# DTR-1_v2021-05-06.net
KiCad netlist of a schematic drawn in EAGLE
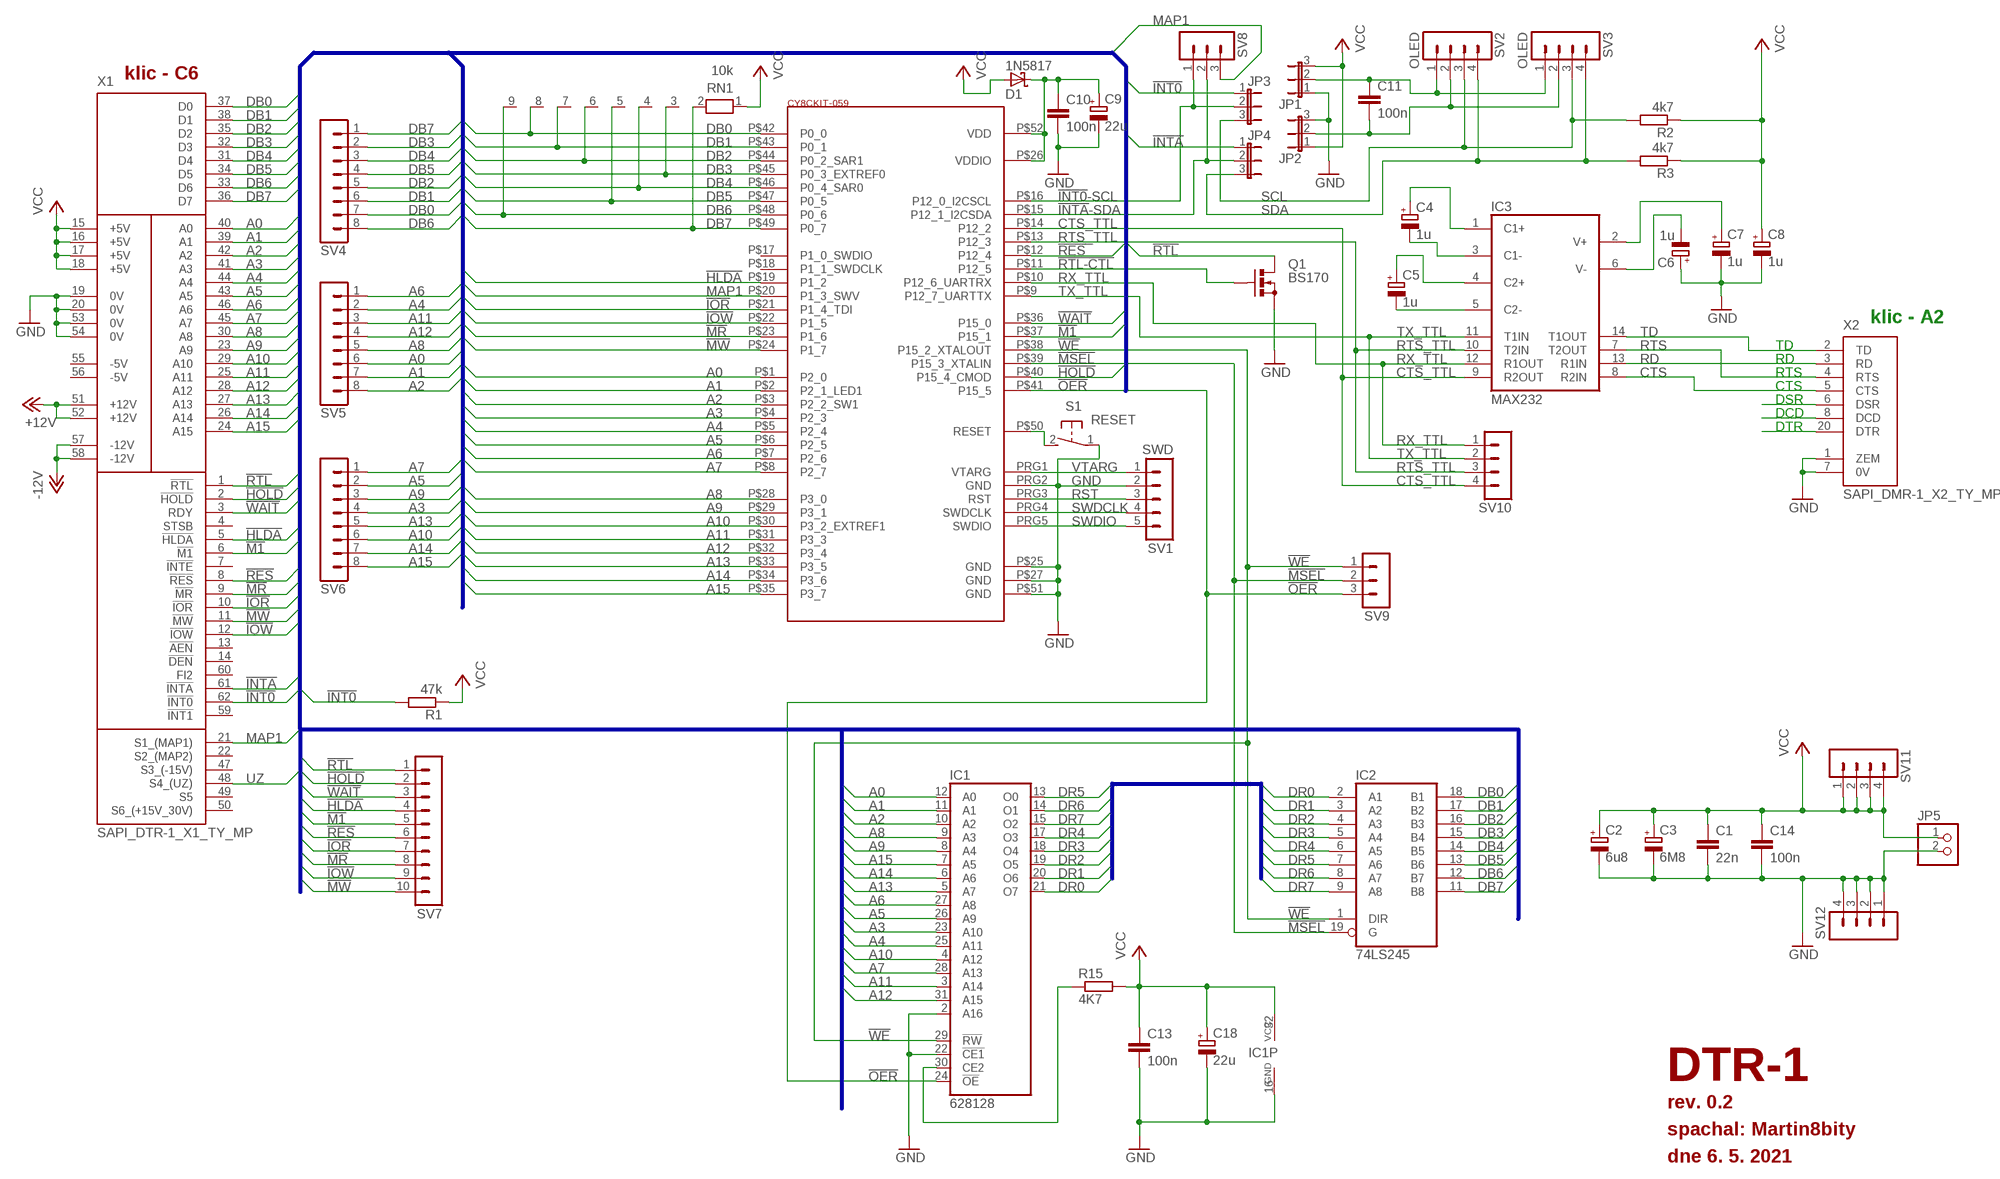
[diagram p0: schematic, sheet 1]

(export (version "E")
  (design (tool "Eeschema 10.0.6"))
  (components
    (comp (ref "C1")
      (value "22n")
      (footprint "eagle-import:C025-024X044")
      (libsource (lib "eagle-import") (part "C-EU025-024X044"))
    )
    (comp (ref "C2")
      (value "6u8")
      (footprint "eagle-import:E5-4")
      (libsource (lib "eagle-import") (part "CPOL-EUE5-4"))
    )
    (comp (ref "C3")
      (value "6M8")
      (footprint "eagle-import:E2,5-5")
      (libsource (lib "eagle-import") (part "CPOL-EUE2.5-5"))
    )
    (comp (ref "C4")
      (value "1u")
      (footprint "eagle-import:E2,5-5")
      (libsource (lib "eagle-import") (part "CPOL-EUE2.5-5"))
    )
    (comp (ref "C5")
      (value "1u")
      (footprint "eagle-import:E2,5-5")
      (libsource (lib "eagle-import") (part "CPOL-EUE2.5-5"))
    )
    (comp (ref "C6")
      (value "1u")
      (footprint "eagle-import:E2,5-5")
      (libsource (lib "eagle-import") (part "CPOL-EUE2.5-5"))
    )
    (comp (ref "C7")
      (value "1u")
      (footprint "eagle-import:E2,5-5")
      (libsource (lib "eagle-import") (part "CPOL-EUE2.5-5"))
    )
    (comp (ref "C8")
      (value "1u")
      (footprint "eagle-import:E2,5-5")
      (libsource (lib "eagle-import") (part "CPOL-EUE2.5-5"))
    )
    (comp (ref "C9")
      (value "22u")
      (footprint "eagle-import:E2,5-5")
      (libsource (lib "eagle-import") (part "CPOL-EUE2.5-5"))
    )
    (comp (ref "C10")
      (value "100n")
      (footprint "eagle-import:C025-024X044")
      (libsource (lib "eagle-import") (part "C-EU025-024X044"))
    )
    (comp (ref "C11")
      (value "100n")
      (footprint "eagle-import:C050-025X075")
      (libsource (lib "eagle-import") (part "C-EU050-025X075"))
    )
    (comp (ref "C13")
      (value "100n")
      (footprint "eagle-import:C025-024X044")
      (libsource (lib "eagle-import") (part "C-EU025-024X044"))
    )
    (comp (ref "C14")
      (value "100n")
      (footprint "eagle-import:C025-024X044")
      (libsource (lib "eagle-import") (part "C-EU025-024X044"))
    )
    (comp (ref "C18")
      (value "22u")
      (footprint "eagle-import:E2,5-5")
      (libsource (lib "eagle-import") (part "CPOL-EUE2.5-5"))
    )
    (comp (ref "D1")
      (value "1N5817")
      (footprint "eagle-import:DO41-7.6")
      (libsource (lib "eagle-import") (part "1N5817-B"))
    )
    (comp (ref "IC1")
      (value "628128")
      (footprint "eagle-import:DIL32")
      (libsource (lib "eagle-import") (part "TC551001CP"))
    )
    (comp (ref "IC2")
      (value "74LS245")
      (footprint "eagle-import:DIL20")
      (libsource (lib "eagle-import") (part "74245NLS"))
    )
    (comp (ref "IC3")
      (value "MAX232")
      (footprint "eagle-import:DIL16")
      (fields (field (name "MF") "MAXIM") (field (name "MPN") "MAX232ACPE+"))
      (libsource (lib "eagle-import") (part "MAX232"))
    )
    (comp (ref "JP1")
      (value "JP2E")
      (footprint "eagle-import:JP2")
      (libsource (lib "eagle-import") (part "JP2E"))
    )
    (comp (ref "JP2")
      (value "JP2E")
      (footprint "eagle-import:JP2")
      (libsource (lib "eagle-import") (part "JP2E"))
    )
    (comp (ref "JP3")
      (value "JP2E")
      (footprint "eagle-import:JP2")
      (libsource (lib "eagle-import") (part "JP2E"))
    )
    (comp (ref "JP4")
      (value "JP2E")
      (footprint "eagle-import:JP2")
      (libsource (lib "eagle-import") (part "JP2E"))
    )
    (comp (ref "JP5")
      (value "PINHD-1X2")
      (footprint "eagle-import:1X02")
      (libsource (lib "eagle-import") (part "PINHD-1X2"))
    )
    (comp (ref "Q1")
      (value "BS170")
      (footprint "eagle-import:SOT54E")
      (libsource (lib "eagle-import") (part "BS170"))
    )
    (comp (ref "R1")
      (value "47k")
      (footprint "eagle-import:0207_10")
      (libsource (lib "eagle-import") (part "R-EU_0207/10"))
    )
    (comp (ref "R2")
      (value "4k7")
      (footprint "eagle-import:0207_10")
      (libsource (lib "eagle-import") (part "R-EU_0207/10"))
    )
    (comp (ref "R3")
      (value "4k7")
      (footprint "eagle-import:0207_10")
      (libsource (lib "eagle-import") (part "R-EU_0207/10"))
    )
    (comp (ref "R15")
      (value "4K7")
      (footprint "eagle-import:0207_10")
      (libsource (lib "eagle-import") (part "R-EU_0207/10"))
    )
    (comp (ref "RN1")
      (value "10k")
      (footprint "eagle-import:RN-9")
      (libsource (lib "eagle-import") (part "RN08"))
    )
    (comp (ref "S1")
      (value "RESET")
      (footprint "eagle-import:B3F-31XX")
      (fields (field (name "MPN") "B3F-3100"))
      (libsource (lib "eagle-import") (part "31-XX"))
    )
    (comp (ref "SV1")
      (value "SWD")
      (footprint "eagle-import:MA05-1")
      (libsource (lib "eagle-import") (part "MA05-1"))
    )
    (comp (ref "SV2")
      (value "OLED")
      (footprint "eagle-import:MA04-1")
      (libsource (lib "eagle-import") (part "MA04-1"))
    )
    (comp (ref "SV3")
      (value "OLED")
      (footprint "eagle-import:MA04-1")
      (libsource (lib "eagle-import") (part "MA04-1"))
    )
    (comp (ref "SV4")
      (value "MA08-1")
      (footprint "eagle-import:MA08-1")
      (libsource (lib "eagle-import") (part "MA08-1"))
    )
    (comp (ref "SV5")
      (value "MA08-1")
      (footprint "eagle-import:MA08-1")
      (libsource (lib "eagle-import") (part "MA08-1"))
    )
    (comp (ref "SV6")
      (value "MA08-1")
      (footprint "eagle-import:MA08-1")
      (libsource (lib "eagle-import") (part "MA08-1"))
    )
    (comp (ref "SV7")
      (value "MA10-1")
      (footprint "eagle-import:MA10-1")
      (libsource (lib "eagle-import") (part "MA10-1"))
    )
    (comp (ref "SV8")
      (value "MA03-1")
      (footprint "eagle-import:MA03-1")
      (libsource (lib "eagle-import") (part "MA03-1"))
    )
    (comp (ref "SV9")
      (value "MA03-1")
      (footprint "eagle-import:MA03-1")
      (libsource (lib "eagle-import") (part "MA03-1"))
    )
    (comp (ref "SV10")
      (value "MA04-1")
      (footprint "eagle-import:MA04-1")
      (libsource (lib "eagle-import") (part "MA04-1"))
    )
    (comp (ref "SV11")
      (value "MA04-1")
      (footprint "eagle-import:MA04-1")
      (libsource (lib "eagle-import") (part "MA04-1"))
    )
    (comp (ref "SV12")
      (value "MA04-1")
      (footprint "eagle-import:MA04-1")
      (libsource (lib "eagle-import") (part "MA04-1"))
    )
    (comp (ref "U$1")
      (value "CY8CKIT-059")
      (footprint "eagle-import:PSOC-KIT-26")
      (libsource (lib "eagle-import") (part "CY8CKIT-059"))
    )
    (comp (ref "X1")
      (value "SAPI_DTR-1_X1_TY_MP")
      (footprint "eagle-import:TY5176211_DTR-1_X1")
      (libsource (lib "eagle-import") (part "SAPI_DTR-1_X1_TY_MP"))
    )
    (comp (ref "X2")
      (value "SAPI_DMR-1_X2_TY_MP")
      (footprint "eagle-import:TY5133011_DMR-1_X2")
      (libsource (lib "eagle-import") (part "SAPI_DMR-1_X2_TY_MP"))
    )
  )
  (nets
    (net (code "1") (name "+12V") (class "Default")
      (node (ref "X1") (pin "51") (pinfunction "+12V_51") (pintype "passive"))
      (node (ref "X1") (pin "52") (pinfunction "+12V_52") (pintype "passive"))
    )
    (net (code "2") (name "-12V") (class "Default")
      (node (ref "X1") (pin "57") (pinfunction "-12V_57") (pintype "passive"))
      (node (ref "X1") (pin "58") (pinfunction "-12V_58") (pintype "passive"))
    )
    (net (code "3") (name "/A0") (class "Default")
      (node (ref "IC1") (pin "12") (pinfunction "A0_12") (pintype "input"))
      (node (ref "SV5") (pin "6") (pinfunction "6_6") (pintype "passive"))
      (node (ref "U$1") (pin "P$1") (pinfunction "P2_0_P$1") (pintype "bidirectional"))
      (node (ref "X1") (pin "40") (pinfunction "A0_40") (pintype "passive"))
    )
    (net (code "4") (name "/A1") (class "Default")
      (node (ref "IC1") (pin "11") (pinfunction "A1_11") (pintype "input"))
      (node (ref "SV5") (pin "7") (pinfunction "7_7") (pintype "passive"))
      (node (ref "U$1") (pin "P$2") (pinfunction "P2_1_LED1_P$2") (pintype "bidirectional"))
      (node (ref "X1") (pin "39") (pinfunction "A1_39") (pintype "passive"))
    )
    (net (code "5") (name "/A2") (class "Default")
      (node (ref "IC1") (pin "10") (pinfunction "A2_10") (pintype "input"))
      (node (ref "SV5") (pin "8") (pinfunction "8_8") (pintype "passive"))
      (node (ref "U$1") (pin "P$3") (pinfunction "P2_2_SW1_P$3") (pintype "bidirectional"))
      (node (ref "X1") (pin "42") (pinfunction "A2_42") (pintype "passive"))
    )
    (net (code "6") (name "/A3") (class "Default")
      (node (ref "IC1") (pin "23") (pinfunction "A10_23") (pintype "input"))
      (node (ref "SV6") (pin "4") (pinfunction "4_4") (pintype "passive"))
      (node (ref "U$1") (pin "P$4") (pinfunction "P2_3_P$4") (pintype "bidirectional"))
      (node (ref "X1") (pin "41") (pinfunction "A3_41") (pintype "passive"))
    )
    (net (code "7") (name "/A4") (class "Default")
      (node (ref "IC1") (pin "25") (pinfunction "A11_25") (pintype "input"))
      (node (ref "SV5") (pin "2") (pinfunction "2_2") (pintype "passive"))
      (node (ref "U$1") (pin "P$5") (pinfunction "P2_4_P$5") (pintype "bidirectional"))
      (node (ref "X1") (pin "44") (pinfunction "A4_44") (pintype "passive"))
    )
    (net (code "8") (name "/A5") (class "Default")
      (node (ref "IC1") (pin "26") (pinfunction "A9_26") (pintype "input"))
      (node (ref "SV6") (pin "2") (pinfunction "2_2") (pintype "passive"))
      (node (ref "U$1") (pin "P$6") (pinfunction "P2_5_P$6") (pintype "bidirectional"))
      (node (ref "X1") (pin "43") (pinfunction "A5_43") (pintype "passive"))
    )
    (net (code "9") (name "/A6") (class "Default")
      (node (ref "IC1") (pin "27") (pinfunction "A8_27") (pintype "input"))
      (node (ref "SV5") (pin "1") (pinfunction "1_1") (pintype "passive"))
      (node (ref "U$1") (pin "P$7") (pinfunction "P2_6_P$7") (pintype "bidirectional"))
      (node (ref "X1") (pin "46") (pinfunction "A6_46") (pintype "passive"))
    )
    (net (code "10") (name "/A7") (class "Default")
      (node (ref "IC1") (pin "28") (pinfunction "A13_28") (pintype "input"))
      (node (ref "SV6") (pin "1") (pinfunction "1_1") (pintype "passive"))
      (node (ref "U$1") (pin "P$8") (pinfunction "P2_7_P$8") (pintype "bidirectional"))
      (node (ref "X1") (pin "45") (pinfunction "A7_45") (pintype "passive"))
    )
    (net (code "11") (name "/A8") (class "Default")
      (node (ref "IC1") (pin "9") (pinfunction "A3_9") (pintype "input"))
      (node (ref "SV5") (pin "5") (pinfunction "5_5") (pintype "passive"))
      (node (ref "U$1") (pin "P$28") (pinfunction "P3_0_P$28") (pintype "bidirectional"))
      (node (ref "X1") (pin "30") (pinfunction "A8_30") (pintype "passive"))
    )
    (net (code "12") (name "/A9") (class "Default")
      (node (ref "IC1") (pin "8") (pinfunction "A4_8") (pintype "input"))
      (node (ref "SV6") (pin "3") (pinfunction "3_3") (pintype "passive"))
      (node (ref "U$1") (pin "P$29") (pinfunction "P3_1_P$29") (pintype "bidirectional"))
      (node (ref "X1") (pin "23") (pinfunction "A9_23") (pintype "passive"))
    )
    (net (code "13") (name "/A10") (class "Default")
      (node (ref "IC1") (pin "4") (pinfunction "A12_4") (pintype "input"))
      (node (ref "SV6") (pin "6") (pinfunction "6_6") (pintype "passive"))
      (node (ref "U$1") (pin "P$30") (pinfunction "P3_2_EXTREF1_P$30") (pintype "bidirectional"))
      (node (ref "X1") (pin "29") (pinfunction "A10_29") (pintype "passive"))
    )
    (net (code "14") (name "/A11") (class "Default")
      (node (ref "IC1") (pin "3") (pinfunction "A14_3") (pintype "input"))
      (node (ref "SV5") (pin "3") (pinfunction "3_3") (pintype "passive"))
      (node (ref "U$1") (pin "P$31") (pinfunction "P3_3_P$31") (pintype "bidirectional"))
      (node (ref "X1") (pin "25") (pinfunction "A11_25") (pintype "passive"))
    )
    (net (code "15") (name "/A12") (class "Default")
      (node (ref "IC1") (pin "31") (pinfunction "A15_31") (pintype "input"))
      (node (ref "SV5") (pin "4") (pinfunction "4_4") (pintype "passive"))
      (node (ref "U$1") (pin "P$32") (pinfunction "P3_4_P$32") (pintype "bidirectional"))
      (node (ref "X1") (pin "28") (pinfunction "A12_28") (pintype "passive"))
    )
    (net (code "16") (name "/A13") (class "Default")
      (node (ref "IC1") (pin "5") (pinfunction "A7_5") (pintype "input"))
      (node (ref "SV6") (pin "5") (pinfunction "5_5") (pintype "passive"))
      (node (ref "U$1") (pin "P$33") (pinfunction "P3_5_P$33") (pintype "bidirectional"))
      (node (ref "X1") (pin "27") (pinfunction "A13_27") (pintype "passive"))
    )
    (net (code "17") (name "/A14") (class "Default")
      (node (ref "IC1") (pin "6") (pinfunction "A6_6") (pintype "input"))
      (node (ref "SV6") (pin "7") (pinfunction "7_7") (pintype "passive"))
      (node (ref "U$1") (pin "P$34") (pinfunction "P3_6_P$34") (pintype "bidirectional"))
      (node (ref "X1") (pin "26") (pinfunction "A14_26") (pintype "passive"))
    )
    (net (code "18") (name "/A15") (class "Default")
      (node (ref "IC1") (pin "7") (pinfunction "A5_7") (pintype "input"))
      (node (ref "SV6") (pin "8") (pinfunction "8_8") (pintype "passive"))
      (node (ref "U$1") (pin "P$35") (pinfunction "P3_7_P$35") (pintype "bidirectional"))
      (node (ref "X1") (pin "24") (pinfunction "A15_24") (pintype "passive"))
    )
    (net (code "19") (name "/CTS") (class "Default")
      (node (ref "IC3") (pin "8") (pinfunction "R2IN_8") (pintype "input"))
      (node (ref "X2") (pin "5") (pinfunction "CTS_5") (pintype "passive"))
    )
    (net (code "20") (name "/CTS_TTL") (class "Default")
      (node (ref "IC3") (pin "9") (pinfunction "R2OUT_9") (pintype "output"))
      (node (ref "SV10") (pin "4") (pinfunction "4_4") (pintype "passive"))
      (node (ref "U$1") (pin "P$14") (pinfunction "P12_2_P$14") (pintype "bidirectional"))
    )
    (net (code "21") (name "/DB0") (class "Default")
      (node (ref "IC2") (pin "18") (pinfunction "B1_18") (pintype "bidirectional"))
      (node (ref "RN1") (pin "8") (pinfunction "8_8") (pintype "passive"))
      (node (ref "SV4") (pin "7") (pinfunction "7_7") (pintype "passive"))
      (node (ref "U$1") (pin "P$42") (pinfunction "P0_0_P$42") (pintype "bidirectional"))
      (node (ref "X1") (pin "37") (pinfunction "D0_37") (pintype "passive"))
    )
    (net (code "22") (name "/DB1") (class "Default")
      (node (ref "IC2") (pin "17") (pinfunction "B2_17") (pintype "bidirectional"))
      (node (ref "RN1") (pin "7") (pinfunction "7_7") (pintype "passive"))
      (node (ref "SV4") (pin "6") (pinfunction "6_6") (pintype "passive"))
      (node (ref "U$1") (pin "P$43") (pinfunction "P0_1_P$43") (pintype "bidirectional"))
      (node (ref "X1") (pin "38") (pinfunction "D1_38") (pintype "passive"))
    )
    (net (code "23") (name "/DB2") (class "Default")
      (node (ref "IC2") (pin "16") (pinfunction "B3_16") (pintype "bidirectional"))
      (node (ref "RN1") (pin "6") (pinfunction "6_6") (pintype "passive"))
      (node (ref "SV4") (pin "5") (pinfunction "5_5") (pintype "passive"))
      (node (ref "U$1") (pin "P$44") (pinfunction "P0_2_SAR1_P$44") (pintype "bidirectional"))
      (node (ref "X1") (pin "35") (pinfunction "D2_35") (pintype "passive"))
    )
    (net (code "24") (name "/DB3") (class "Default")
      (node (ref "IC2") (pin "15") (pinfunction "B4_15") (pintype "bidirectional"))
      (node (ref "RN1") (pin "3") (pinfunction "3_3") (pintype "passive"))
      (node (ref "SV4") (pin "2") (pinfunction "2_2") (pintype "passive"))
      (node (ref "U$1") (pin "P$45") (pinfunction "P0_3_EXTREF0_P$45") (pintype "bidirectional"))
      (node (ref "X1") (pin "32") (pinfunction "D3_32") (pintype "passive"))
    )
    (net (code "25") (name "/DB4") (class "Default")
      (node (ref "IC2") (pin "14") (pinfunction "B5_14") (pintype "bidirectional"))
      (node (ref "RN1") (pin "4") (pinfunction "4_4") (pintype "passive"))
      (node (ref "SV4") (pin "3") (pinfunction "3_3") (pintype "passive"))
      (node (ref "U$1") (pin "P$46") (pinfunction "P0_4_SAR0_P$46") (pintype "bidirectional"))
      (node (ref "X1") (pin "31") (pinfunction "D4_31") (pintype "passive"))
    )
    (net (code "26") (name "/DB5") (class "Default")
      (node (ref "IC2") (pin "13") (pinfunction "B6_13") (pintype "bidirectional"))
      (node (ref "RN1") (pin "5") (pinfunction "5_5") (pintype "passive"))
      (node (ref "SV4") (pin "4") (pinfunction "4_4") (pintype "passive"))
      (node (ref "U$1") (pin "P$47") (pinfunction "P0_5_P$47") (pintype "bidirectional"))
      (node (ref "X1") (pin "34") (pinfunction "D5_34") (pintype "passive"))
    )
    (net (code "27") (name "/DB6") (class "Default")
      (node (ref "IC2") (pin "12") (pinfunction "B7_12") (pintype "bidirectional"))
      (node (ref "RN1") (pin "9") (pinfunction "9_9") (pintype "passive"))
      (node (ref "SV4") (pin "8") (pinfunction "8_8") (pintype "passive"))
      (node (ref "U$1") (pin "P$48") (pinfunction "P0_6_P$48") (pintype "bidirectional"))
      (node (ref "X1") (pin "33") (pinfunction "D6_33") (pintype "passive"))
    )
    (net (code "28") (name "/DB7") (class "Default")
      (node (ref "IC2") (pin "11") (pinfunction "B8_11") (pintype "bidirectional"))
      (node (ref "RN1") (pin "2") (pinfunction "2_2") (pintype "passive"))
      (node (ref "SV4") (pin "1") (pinfunction "1_1") (pintype "passive"))
      (node (ref "U$1") (pin "P$49") (pinfunction "P0_7_P$49") (pintype "bidirectional"))
      (node (ref "X1") (pin "36") (pinfunction "D7_36") (pintype "passive"))
    )
    (net (code "29") (name "/DCD") (class "Default")
      (node (ref "X2") (pin "8") (pinfunction "DCD_8") (pintype "passive"))
    )
    (net (code "30") (name "/DR0") (class "Default")
      (node (ref "IC1") (pin "21") (pinfunction "O7_21") (pintype "tri_state"))
      (node (ref "IC2") (pin "2") (pinfunction "A1_2") (pintype "bidirectional"))
    )
    (net (code "31") (name "/DR1") (class "Default")
      (node (ref "IC1") (pin "20") (pinfunction "O6_20") (pintype "tri_state"))
      (node (ref "IC2") (pin "3") (pinfunction "A2_3") (pintype "bidirectional"))
    )
    (net (code "32") (name "/DR2") (class "Default")
      (node (ref "IC1") (pin "19") (pinfunction "O5_19") (pintype "tri_state"))
      (node (ref "IC2") (pin "4") (pinfunction "A3_4") (pintype "bidirectional"))
    )
    (net (code "33") (name "/DR3") (class "Default")
      (node (ref "IC1") (pin "18") (pinfunction "O4_18") (pintype "tri_state"))
      (node (ref "IC2") (pin "5") (pinfunction "A4_5") (pintype "bidirectional"))
    )
    (net (code "34") (name "/DR4") (class "Default")
      (node (ref "IC1") (pin "17") (pinfunction "O3_17") (pintype "tri_state"))
      (node (ref "IC2") (pin "6") (pinfunction "A5_6") (pintype "bidirectional"))
    )
    (net (code "35") (name "/DR5") (class "Default")
      (node (ref "IC1") (pin "13") (pinfunction "O0_13") (pintype "tri_state"))
      (node (ref "IC2") (pin "7") (pinfunction "A6_7") (pintype "bidirectional"))
    )
    (net (code "36") (name "/DR6") (class "Default")
      (node (ref "IC1") (pin "14") (pinfunction "O1_14") (pintype "tri_state"))
      (node (ref "IC2") (pin "8") (pinfunction "A7_8") (pintype "bidirectional"))
    )
    (net (code "37") (name "/DR7") (class "Default")
      (node (ref "IC1") (pin "15") (pinfunction "O2_15") (pintype "tri_state"))
      (node (ref "IC2") (pin "9") (pinfunction "A8_9") (pintype "bidirectional"))
    )
    (net (code "38") (name "/DSR") (class "Default")
      (node (ref "X2") (pin "6") (pinfunction "DSR_6") (pintype "passive"))
    )
    (net (code "39") (name "/DTR") (class "Default")
      (node (ref "X2") (pin "20") (pinfunction "DTR_20") (pintype "passive"))
    )
    (net (code "40") (name "/MAP1") (class "Default")
      (node (ref "SV8") (pin "3") (pinfunction "3_3") (pintype "passive"))
      (node (ref "U$1") (pin "P$20") (pinfunction "P1_3_SWV_P$20") (pintype "bidirectional"))
      (node (ref "X1") (pin "21") (pinfunction "S1_(MAP1)_21") (pintype "passive"))
    )
    (net (code "41") (name "/RD") (class "Default")
      (node (ref "IC3") (pin "13") (pinfunction "R1IN_13") (pintype "input"))
      (node (ref "X2") (pin "3") (pinfunction "RD_3") (pintype "passive"))
    )
    (net (code "42") (name "/RST") (class "Default")
      (node (ref "SV1") (pin "3") (pinfunction "3_3") (pintype "passive"))
      (node (ref "U$1") (pin "PRG3") (pinfunction "RST_PRG3") (pintype "bidirectional"))
    )
    (net (code "43") (name "/RTS") (class "Default")
      (node (ref "IC3") (pin "7") (pinfunction "T2OUT_7") (pintype "output"))
      (node (ref "X2") (pin "4") (pinfunction "RTS_4") (pintype "passive"))
    )
    (net (code "44") (name "/RTS_TTL") (class "Default")
      (node (ref "IC3") (pin "10") (pinfunction "T2IN_10") (pintype "input"))
      (node (ref "SV10") (pin "3") (pinfunction "3_3") (pintype "passive"))
      (node (ref "U$1") (pin "P$13") (pinfunction "P12_3_P$13") (pintype "bidirectional"))
    )
    (net (code "45") (name "/RX_TTL") (class "Default")
      (node (ref "IC3") (pin "12") (pinfunction "R1OUT_12") (pintype "output"))
      (node (ref "SV10") (pin "1") (pinfunction "1_1") (pintype "passive"))
      (node (ref "U$1") (pin "P$10") (pinfunction "P12_6_UARTRX_P$10") (pintype "bidirectional"))
    )
    (net (code "46") (name "/SCL") (class "Default")
      (node (ref "JP3") (pin "3") (pinfunction "3_3") (pintype "passive"))
      (node (ref "R2") (pin "2") (pinfunction "2_2") (pintype "passive"))
      (node (ref "SV2") (pin "3") (pinfunction "3_3") (pintype "passive"))
      (node (ref "SV3") (pin "3") (pinfunction "3_3") (pintype "passive"))
    )
    (net (code "47") (name "/SDA") (class "Default")
      (node (ref "JP4") (pin "3") (pinfunction "3_3") (pintype "passive"))
      (node (ref "R3") (pin "2") (pinfunction "2_2") (pintype "passive"))
      (node (ref "SV2") (pin "4") (pinfunction "4_4") (pintype "passive"))
      (node (ref "SV3") (pin "4") (pinfunction "4_4") (pintype "passive"))
    )
    (net (code "48") (name "/SWDCLK") (class "Default")
      (node (ref "SV1") (pin "4") (pinfunction "4_4") (pintype "passive"))
      (node (ref "U$1") (pin "PRG4") (pinfunction "SWDCLK_PRG4") (pintype "bidirectional"))
    )
    (net (code "49") (name "/SWDIO") (class "Default")
      (node (ref "SV1") (pin "5") (pinfunction "5_5") (pintype "passive"))
      (node (ref "U$1") (pin "PRG5") (pinfunction "SWDIO_PRG5") (pintype "bidirectional"))
    )
    (net (code "50") (name "/TD") (class "Default")
      (node (ref "IC3") (pin "14") (pinfunction "T1OUT_14") (pintype "output"))
      (node (ref "X2") (pin "2") (pinfunction "TD_2") (pintype "passive"))
    )
    (net (code "51") (name "/TX_TTL") (class "Default")
      (node (ref "IC3") (pin "11") (pinfunction "T1IN_11") (pintype "input"))
      (node (ref "SV10") (pin "2") (pinfunction "2_2") (pintype "passive"))
      (node (ref "U$1") (pin "P$9") (pinfunction "P12_7_UARTTX_P$9") (pintype "bidirectional"))
    )
    (net (code "52") (name "/UZ") (class "Default")
      (node (ref "X1") (pin "48") (pinfunction "S4_(UZ)_48") (pintype "passive"))
    )
    (net (code "53") (name "/VTARG") (class "Default")
      (node (ref "SV1") (pin "1") (pinfunction "1_1") (pintype "passive"))
      (node (ref "U$1") (pin "PRG1") (pinfunction "VTARG_PRG1") (pintype "power_in"))
    )
    (net (code "54") (name "/~{HLDA}") (class "Default")
      (node (ref "SV7") (pin "4") (pinfunction "4_4") (pintype "passive"))
      (node (ref "U$1") (pin "P$19") (pinfunction "P1_2_P$19") (pintype "bidirectional"))
      (node (ref "X1") (pin "5") (pinfunction "~{HLDA}_5") (pintype "passive"))
    )
    (net (code "55") (name "/~{HOLD}") (class "Default")
      (node (ref "SV7") (pin "2") (pinfunction "2_2") (pintype "passive"))
      (node (ref "U$1") (pin "P$40") (pinfunction "P15_4_CMOD_P$40") (pintype "bidirectional"))
      (node (ref "X1") (pin "2") (pinfunction "~{HOLD}_2") (pintype "passive"))
    )
    (net (code "56") (name "/~{INT0}") (class "Default")
      (node (ref "JP3") (pin "1") (pinfunction "1_1") (pintype "passive"))
      (node (ref "R1") (pin "2") (pinfunction "2_2") (pintype "passive"))
      (node (ref "X1") (pin "62") (pinfunction "~{INT0}_62") (pintype "passive"))
    )
    (net (code "57") (name "/~{INT0}-SCL") (class "Default")
      (node (ref "JP3") (pin "2") (pinfunction "2_2") (pintype "passive"))
      (node (ref "SV8") (pin "1") (pinfunction "1_1") (pintype "passive"))
      (node (ref "U$1") (pin "P$16") (pinfunction "P12_0_I2CSCL_P$16") (pintype "bidirectional"))
    )
    (net (code "58") (name "/~{INTA}") (class "Default")
      (node (ref "JP4") (pin "1") (pinfunction "1_1") (pintype "passive"))
      (node (ref "X1") (pin "61") (pinfunction "~{INTA}_61") (pintype "passive"))
    )
    (net (code "59") (name "/~{INTA}-SDA") (class "Default")
      (node (ref "JP4") (pin "2") (pinfunction "2_2") (pintype "passive"))
      (node (ref "SV8") (pin "2") (pinfunction "2_2") (pintype "passive"))
      (node (ref "U$1") (pin "P$15") (pinfunction "P12_1_I2CSDA_P$15") (pintype "bidirectional"))
    )
    (net (code "60") (name "/~{IOR}") (class "Default")
      (node (ref "SV7") (pin "7") (pinfunction "7_7") (pintype "passive"))
      (node (ref "U$1") (pin "P$21") (pinfunction "P1_4_TDI_P$21") (pintype "bidirectional"))
      (node (ref "X1") (pin "10") (pinfunction "~{IOR}_10") (pintype "passive"))
    )
    (net (code "61") (name "/~{IOW}") (class "Default")
      (node (ref "SV7") (pin "9") (pinfunction "9_9") (pintype "passive"))
      (node (ref "U$1") (pin "P$22") (pinfunction "P1_5_P$22") (pintype "bidirectional"))
      (node (ref "X1") (pin "12") (pinfunction "~{IOW}_12") (pintype "passive"))
    )
    (net (code "62") (name "/~{M1}") (class "Default")
      (node (ref "SV7") (pin "5") (pinfunction "5_5") (pintype "passive"))
      (node (ref "U$1") (pin "P$37") (pinfunction "P15_1_P$37") (pintype "bidirectional"))
      (node (ref "X1") (pin "6") (pinfunction "~{M1}_6") (pintype "passive"))
    )
    (net (code "63") (name "/~{MR}") (class "Default")
      (node (ref "SV7") (pin "8") (pinfunction "8_8") (pintype "passive"))
      (node (ref "U$1") (pin "P$23") (pinfunction "P1_6_P$23") (pintype "bidirectional"))
      (node (ref "X1") (pin "9") (pinfunction "~{MR}_9") (pintype "passive"))
    )
    (net (code "64") (name "/~{MSEL}") (class "Default")
      (node (ref "IC2") (pin "19") (pinfunction "G_19") (pintype "input"))
      (node (ref "SV9") (pin "2") (pinfunction "2_2") (pintype "passive"))
      (node (ref "U$1") (pin "P$39") (pinfunction "P15_3_XTALIN_P$39") (pintype "bidirectional"))
    )
    (net (code "65") (name "/~{MW}") (class "Default")
      (node (ref "SV7") (pin "10") (pinfunction "10_10") (pintype "passive"))
      (node (ref "U$1") (pin "P$24") (pinfunction "P1_7_P$24") (pintype "bidirectional"))
      (node (ref "X1") (pin "11") (pinfunction "~{MW}_11") (pintype "passive"))
    )
    (net (code "66") (name "/~{OER}") (class "Default")
      (node (ref "IC1") (pin "24") (pinfunction "~{OE}_24") (pintype "input"))
      (node (ref "SV9") (pin "3") (pinfunction "3_3") (pintype "passive"))
      (node (ref "U$1") (pin "P$41") (pinfunction "P15_5_P$41") (pintype "bidirectional"))
    )
    (net (code "67") (name "/~{RES}") (class "Default")
      (node (ref "SV7") (pin "6") (pinfunction "6_6") (pintype "passive"))
      (node (ref "U$1") (pin "P$12") (pinfunction "P12_4_P$12") (pintype "bidirectional"))
      (node (ref "X1") (pin "8") (pinfunction "~{RES}_8") (pintype "passive"))
    )
    (net (code "68") (name "/~{RTL-CTL}") (class "Default")
      (node (ref "Q1") (pin "G") (pinfunction "G_G") (pintype "passive"))
      (node (ref "U$1") (pin "P$11") (pinfunction "P12_5_P$11") (pintype "bidirectional"))
    )
    (net (code "69") (name "/~{RTL}") (class "Default")
      (node (ref "Q1") (pin "D") (pinfunction "D_D") (pintype "passive"))
      (node (ref "SV7") (pin "1") (pinfunction "1_1") (pintype "passive"))
      (node (ref "X1") (pin "1") (pinfunction "~{RTL}_1") (pintype "passive"))
    )
    (net (code "70") (name "/~{WAIT}") (class "Default")
      (node (ref "SV7") (pin "3") (pinfunction "3_3") (pintype "passive"))
      (node (ref "U$1") (pin "P$36") (pinfunction "P15_0_P$36") (pintype "bidirectional"))
      (node (ref "X1") (pin "3") (pinfunction "RDY_3") (pintype "passive"))
    )
    (net (code "71") (name "/~{WE}") (class "Default")
      (node (ref "IC1") (pin "29") (pinfunction "~{RW}_29") (pintype "input"))
      (node (ref "IC2") (pin "1") (pinfunction "DIR_1") (pintype "input"))
      (node (ref "SV9") (pin "1") (pinfunction "1_1") (pintype "passive"))
      (node (ref "U$1") (pin "P$38") (pinfunction "P15_2_XTALOUT_P$38") (pintype "bidirectional"))
    )
    (net (code "72") (name "GND") (class "Default")
      (node (ref "C1") (pin "2") (pinfunction "2_2") (pintype "passive"))
      (node (ref "C10") (pin "2") (pinfunction "2_2") (pintype "passive"))
      (node (ref "C13") (pin "2") (pinfunction "2_2") (pintype "passive"))
      (node (ref "C14") (pin "2") (pinfunction "2_2") (pintype "passive"))
      (node (ref "C18") (pin "-") (pinfunction "-_-") (pintype "passive"))
      (node (ref "C2") (pin "-") (pinfunction "-_-") (pintype "passive"))
      (node (ref "C3") (pin "-") (pinfunction "-_-") (pintype "passive"))
      (node (ref "C6") (pin "+") (pinfunction "+_+") (pintype "passive"))
      (node (ref "C7") (pin "-") (pinfunction "-_-") (pintype "passive"))
      (node (ref "C8") (pin "-") (pinfunction "-_-") (pintype "passive"))
      (node (ref "C9") (pin "-") (pinfunction "-_-") (pintype "passive"))
      (node (ref "IC1") (pin "16") (pinfunction "GND_16") (pintype "power_in"))
      (node (ref "IC1") (pin "2") (pinfunction "A16_2") (pintype "input"))
      (node (ref "IC1") (pin "22") (pinfunction "~{CE1}_22") (pintype "input"))
      (node (ref "JP1") (pin "1") (pinfunction "1_1") (pintype "passive"))
      (node (ref "JP2") (pin "3") (pinfunction "3_3") (pintype "passive"))
      (node (ref "JP5") (pin "2") (pinfunction "2_2") (pintype "passive"))
      (node (ref "Q1") (pin "S") (pinfunction "S_S") (pintype "passive"))
      (node (ref "S1") (pin "1") (pinfunction "P_1") (pintype "passive"))
      (node (ref "SV1") (pin "2") (pinfunction "2_2") (pintype "passive"))
      (node (ref "SV12") (pin "1") (pinfunction "1_1") (pintype "passive"))
      (node (ref "SV12") (pin "2") (pinfunction "2_2") (pintype "passive"))
      (node (ref "SV12") (pin "3") (pinfunction "3_3") (pintype "passive"))
      (node (ref "SV12") (pin "4") (pinfunction "4_4") (pintype "passive"))
      (node (ref "U$1") (pin "P$25") (pinfunction "GND_P$25") (pintype "power_in"))
      (node (ref "U$1") (pin "P$27") (pinfunction "GND_P$27") (pintype "power_in"))
      (node (ref "U$1") (pin "P$51") (pinfunction "GND_P$51") (pintype "power_in"))
      (node (ref "U$1") (pin "PRG2") (pinfunction "GND_PRG2") (pintype "power_in"))
      (node (ref "X1") (pin "19") (pinfunction "0V_19") (pintype "passive"))
      (node (ref "X1") (pin "20") (pinfunction "0V_20") (pintype "passive"))
      (node (ref "X1") (pin "53") (pinfunction "0V_53") (pintype "passive"))
      (node (ref "X1") (pin "54") (pinfunction "0V_54") (pintype "passive"))
      (node (ref "X2") (pin "1") (pinfunction "ZEM_1") (pintype "passive"))
      (node (ref "X2") (pin "7") (pinfunction "0V_7") (pintype "passive"))
    )
    (net (code "73") (name "Net-(C11-Pad1)") (class "Default")
      (node (ref "C11") (pin "1") (pinfunction "1_1") (pintype "passive"))
      (node (ref "JP1") (pin "2") (pinfunction "2_2") (pintype "passive"))
      (node (ref "SV2") (pin "1") (pinfunction "1_1") (pintype "passive"))
      (node (ref "SV3") (pin "1") (pinfunction "1_1") (pintype "passive"))
    )
    (net (code "74") (name "Net-(C11-Pad2)") (class "Default")
      (node (ref "C11") (pin "2") (pinfunction "2_2") (pintype "passive"))
      (node (ref "JP2") (pin "2") (pinfunction "2_2") (pintype "passive"))
      (node (ref "SV2") (pin "2") (pinfunction "2_2") (pintype "passive"))
      (node (ref "SV3") (pin "2") (pinfunction "2_2") (pintype "passive"))
    )
    (net (code "75") (name "Net-(IC1B-CE2)") (class "Default")
      (node (ref "IC1") (pin "30") (pinfunction "CE2_30") (pintype "input"))
      (node (ref "R15") (pin "1") (pinfunction "1_1") (pintype "passive"))
    )
    (net (code "76") (name "Net-(IC3A-C1+)") (class "Default")
      (node (ref "C4") (pin "+") (pinfunction "+_+") (pintype "passive"))
      (node (ref "IC3") (pin "1") (pinfunction "C1+_1") (pintype "bidirectional"))
    )
    (net (code "77") (name "Net-(IC3A-C1-)") (class "Default")
      (node (ref "C4") (pin "-") (pinfunction "-_-") (pintype "passive"))
      (node (ref "IC3") (pin "3") (pinfunction "C1-_3") (pintype "bidirectional"))
    )
    (net (code "78") (name "Net-(IC3A-C2+)") (class "Default")
      (node (ref "C5") (pin "+") (pinfunction "+_+") (pintype "passive"))
      (node (ref "IC3") (pin "4") (pinfunction "C2+_4") (pintype "bidirectional"))
    )
    (net (code "79") (name "Net-(IC3A-C2-)") (class "Default")
      (node (ref "C5") (pin "-") (pinfunction "-_-") (pintype "passive"))
      (node (ref "IC3") (pin "5") (pinfunction "C2-_5") (pintype "bidirectional"))
    )
    (net (code "80") (name "Net-(IC3A-V+)") (class "Default")
      (node (ref "C7") (pin "+") (pinfunction "+_+") (pintype "passive"))
      (node (ref "IC3") (pin "2") (pinfunction "V+_2") (pintype "bidirectional"))
    )
    (net (code "81") (name "Net-(IC3A-V-)") (class "Default")
      (node (ref "C6") (pin "-") (pinfunction "-_-") (pintype "passive"))
      (node (ref "IC3") (pin "6") (pinfunction "V-_6") (pintype "bidirectional"))
    )
    (net (code "82") (name "Net-(S1-S)") (class "Default")
      (node (ref "S1") (pin "2") (pinfunction "S_2") (pintype "passive"))
      (node (ref "U$1") (pin "P$50") (pinfunction "RESET_P$50") (pintype "bidirectional"))
    )
    (net (code "83") (name "Net-(U$1-VDD)") (class "Default")
      (node (ref "C10") (pin "1") (pinfunction "1_1") (pintype "passive"))
      (node (ref "C9") (pin "+") (pinfunction "+_+") (pintype "passive"))
      (node (ref "D1") (pin "C") (pinfunction "C_C") (pintype "passive"))
      (node (ref "U$1") (pin "P$26") (pinfunction "VDDIO_P$26") (pintype "power_in"))
      (node (ref "U$1") (pin "P$52") (pinfunction "VDD_P$52") (pintype "power_in"))
    )
    (net (code "84") (name "VCC") (class "Default")
      (node (ref "C1") (pin "1") (pinfunction "1_1") (pintype "passive"))
      (node (ref "C13") (pin "1") (pinfunction "1_1") (pintype "passive"))
      (node (ref "C14") (pin "1") (pinfunction "1_1") (pintype "passive"))
      (node (ref "C18") (pin "+") (pinfunction "+_+") (pintype "passive"))
      (node (ref "C2") (pin "+") (pinfunction "+_+") (pintype "passive"))
      (node (ref "C3") (pin "+") (pinfunction "+_+") (pintype "passive"))
      (node (ref "C8") (pin "+") (pinfunction "+_+") (pintype "passive"))
      (node (ref "D1") (pin "A") (pinfunction "A_A") (pintype "passive"))
      (node (ref "IC1") (pin "32") (pinfunction "VCC_32") (pintype "power_in"))
      (node (ref "JP1") (pin "3") (pinfunction "3_3") (pintype "passive"))
      (node (ref "JP2") (pin "1") (pinfunction "1_1") (pintype "passive"))
      (node (ref "JP5") (pin "1") (pinfunction "1_1") (pintype "passive"))
      (node (ref "R1") (pin "1") (pinfunction "1_1") (pintype "passive"))
      (node (ref "R15") (pin "2") (pinfunction "2_2") (pintype "passive"))
      (node (ref "R2") (pin "1") (pinfunction "1_1") (pintype "passive"))
      (node (ref "R3") (pin "1") (pinfunction "1_1") (pintype "passive"))
      (node (ref "RN1") (pin "1") (pinfunction "1_1") (pintype "passive"))
      (node (ref "SV11") (pin "1") (pinfunction "1_1") (pintype "passive"))
      (node (ref "SV11") (pin "2") (pinfunction "2_2") (pintype "passive"))
      (node (ref "SV11") (pin "3") (pinfunction "3_3") (pintype "passive"))
      (node (ref "SV11") (pin "4") (pinfunction "4_4") (pintype "passive"))
      (node (ref "X1") (pin "15") (pinfunction "+5V_15") (pintype "passive"))
      (node (ref "X1") (pin "16") (pinfunction "+5V_16") (pintype "passive"))
      (node (ref "X1") (pin "17") (pinfunction "+5V_17") (pintype "passive"))
      (node (ref "X1") (pin "18") (pinfunction "+5V_18") (pintype "passive"))
    )
    (net (code "85") (name "unconnected-(U$1-P1_0_SWDIO-PadP$17)") (class "Default")
      (node (ref "U$1") (pin "P$17") (pinfunction "P1_0_SWDIO_P$17") (pintype "bidirectional"))
    )
    (net (code "86") (name "unconnected-(U$1-P1_1_SWDCLK-PadP$18)") (class "Default")
      (node (ref "U$1") (pin "P$18") (pinfunction "P1_1_SWDCLK_P$18") (pintype "bidirectional"))
    )
    (net (code "87") (name "unconnected-(X1--5V-Pad55)") (class "Default")
      (node (ref "X1") (pin "55") (pinfunction "-5V_55") (pintype "passive"))
    )
    (net (code "88") (name "unconnected-(X1--5V-Pad56)") (class "Default")
      (node (ref "X1") (pin "56") (pinfunction "-5V_56") (pintype "passive"))
    )
    (net (code "89") (name "unconnected-(X1-FI2-Pad60)") (class "Default")
      (node (ref "X1") (pin "60") (pinfunction "FI2_60") (pintype "passive"))
    )
    (net (code "90") (name "unconnected-(X1-S2_(MAP2)-Pad22)") (class "Default")
      (node (ref "X1") (pin "22") (pinfunction "S2_(MAP2)_22") (pintype "passive"))
    )
    (net (code "91") (name "unconnected-(X1-S3_(-15V)-Pad47)") (class "Default")
      (node (ref "X1") (pin "47") (pinfunction "S3_(-15V)_47") (pintype "passive"))
    )
    (net (code "92") (name "unconnected-(X1-S5-Pad49)") (class "Default")
      (node (ref "X1") (pin "49") (pinfunction "S5_49") (pintype "passive"))
    )
    (net (code "93") (name "unconnected-(X1-S6_(+15V_30V)-Pad50)") (class "Default")
      (node (ref "X1") (pin "50") (pinfunction "S6_(+15V_30V)_50") (pintype "passive"))
    )
    (net (code "94") (name "unconnected-(X1-STSB-Pad4)") (class "Default")
      (node (ref "X1") (pin "4") (pinfunction "STSB_4") (pintype "passive"))
    )
    (net (code "95") (name "unconnected-(X1-~{AEN}-Pad13)") (class "Default")
      (node (ref "X1") (pin "13") (pinfunction "~{AEN}_13") (pintype "passive"))
    )
    (net (code "96") (name "unconnected-(X1-~{DEN}-Pad14)") (class "Default")
      (node (ref "X1") (pin "14") (pinfunction "~{DEN}_14") (pintype "passive"))
    )
    (net (code "97") (name "unconnected-(X1-~{INT1}-Pad59)") (class "Default")
      (node (ref "X1") (pin "59") (pinfunction "~{INT1}_59") (pintype "passive"))
    )
    (net (code "98") (name "unconnected-(X1-~{INTE}-Pad7)") (class "Default")
      (node (ref "X1") (pin "7") (pinfunction "~{INTE}_7") (pintype "passive"))
    )
  )
)
